# SCH_NFC-Card_2024-10-16.net
KiCad netlist of a schematic drawn in EasyEDA
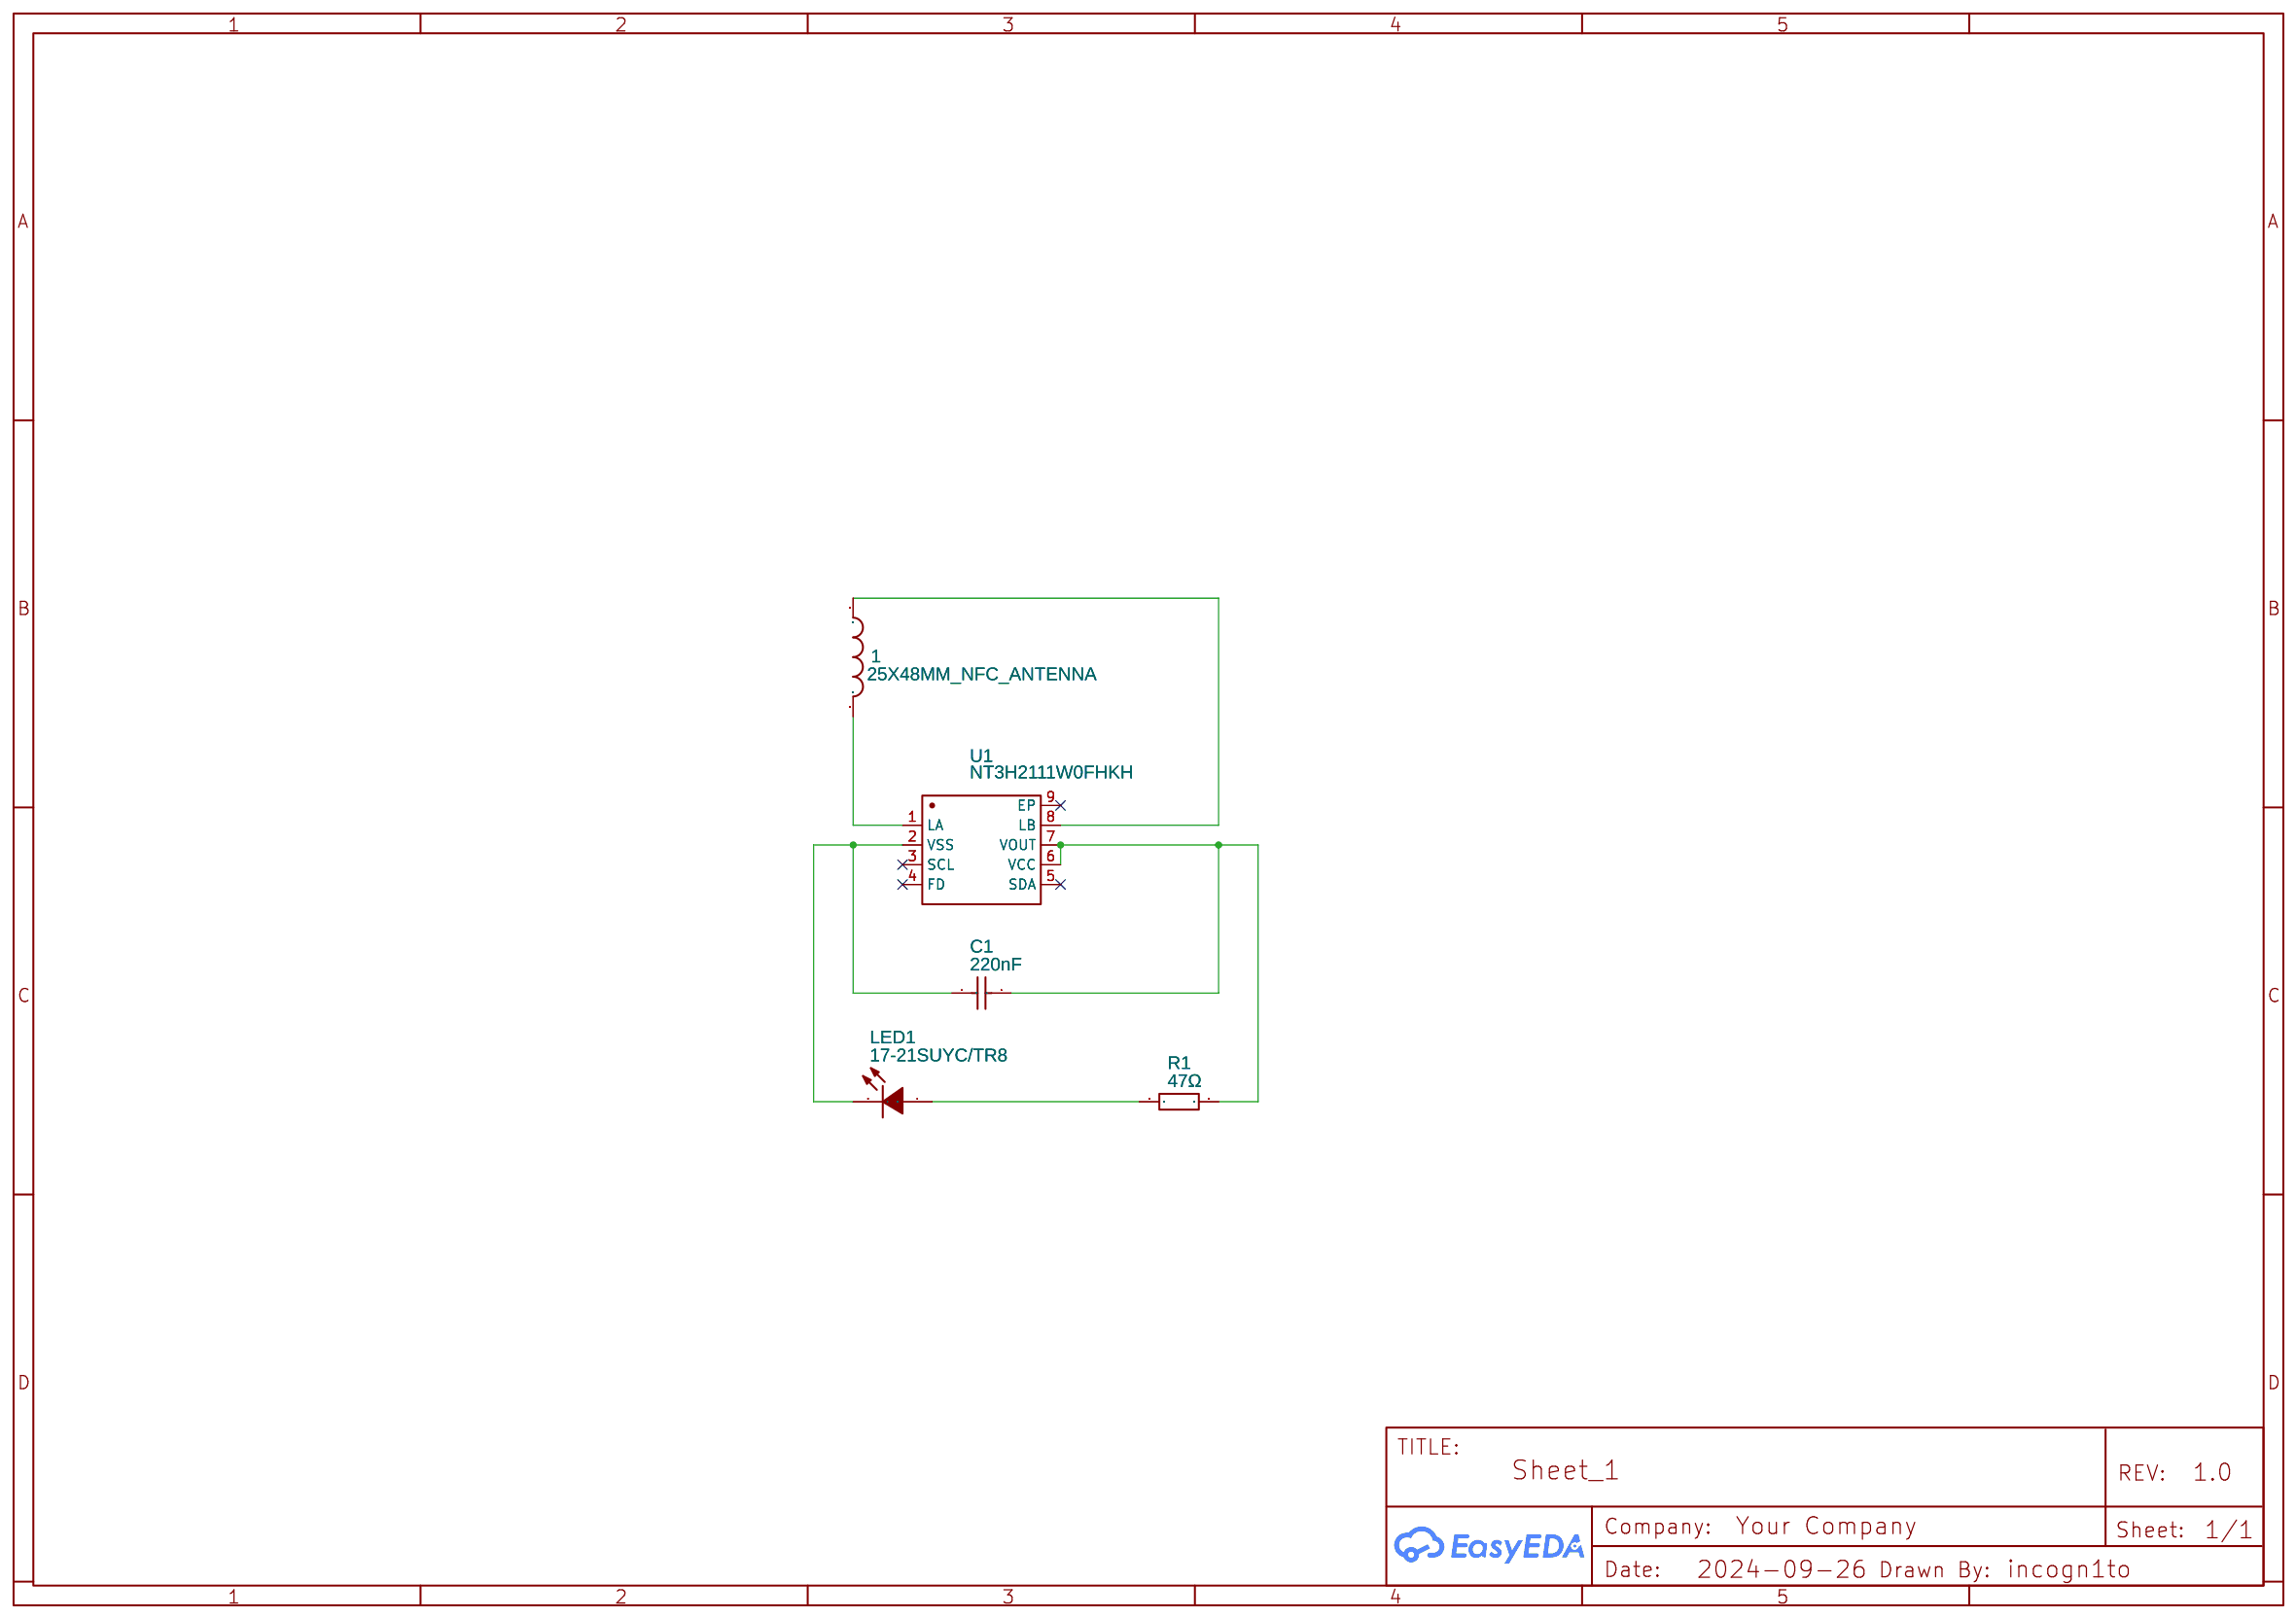
[diagram p0: schematic sheet]

(export (version "E")
  (design (tool "Eeschema 10.0.6"))
  (components
    (comp (ref "1") (value "25X48MM_NFC_ANTENNA") (libsource (lib "") (part "25X48MM_NFC_ANTENNA")))
    (comp (ref "C1")
      (value "220nF")
      (fields
        (field (name "Manufacturer Part") "CL10B224KA8NNNC")
        (field (name "Manufacturer") "SAMSUNG(三星)")
      )
      (libsource (lib "") (part "CL10B224KA8NNNC"))
    )
    (comp (ref "LED1")
      (value "17-21SUYC/TR8")
      (fields (field (name "Manufacturer Part") "KT-0805黄灯") (field (name "Manufacturer") "KENTO"))
      (libsource (lib "") (part "17-21SUYC/TR8"))
    )
    (comp (ref "R1")
      (value "47Ω")
      (fields
        (field (name "Manufacturer Part") "0603WAF470JT5E")
        (field (name "Manufacturer") "UNI-ROYAL(厚声)")
      )
      (libsource (lib "") (part "0603WAF470JT5E"))
    )
    (comp (ref "U1")
      (value "NT3H2111W0FHKH")
      (fields (field (name "Manufacturer") "NXP(恩智浦)"))
      (libsource (lib "") (part "NT3H2111W0FHKH"))
    )
  )
  (nets
    (net (code "1") (name "Net-(LED1-+)") (class "Default")
      (node (ref "LED1") (pin "1") (pinfunction "+_1") (pintype "unspecified"))
      (node (ref "R1") (pin "1") (pinfunction "1_1") (pintype "input"))
    )
    (net (code "2") (name "Net-(LED1--)") (class "Default")
      (node (ref "C1") (pin "1") (pinfunction "1_1") (pintype "input"))
      (node (ref "LED1") (pin "2") (pinfunction "-_2") (pintype "unspecified"))
      (node (ref "U1") (pin "2") (pinfunction "VSS_2") (pintype "unspecified"))
    )
    (net (code "3") (name "Net-(U1-LA)") (class "Default")
      (node (ref "1") (pin "P$2") (pinfunction "P$2_P$2") (pintype "bidirectional"))
      (node (ref "U1") (pin "1") (pinfunction "LA_1") (pintype "unspecified"))
    )
    (net (code "4") (name "Net-(U1-LB)") (class "Default")
      (node (ref "1") (pin "P$1") (pinfunction "P$1_P$1") (pintype "bidirectional"))
      (node (ref "U1") (pin "8") (pinfunction "LB_8") (pintype "unspecified"))
    )
    (net (code "5") (name "Net-(U1-VCC)") (class "Default")
      (node (ref "C1") (pin "2") (pinfunction "2_2") (pintype "input"))
      (node (ref "R1") (pin "2") (pinfunction "2_2") (pintype "input"))
      (node (ref "U1") (pin "6") (pinfunction "VCC_6") (pintype "unspecified"))
      (node (ref "U1") (pin "7") (pinfunction "VOUT_7") (pintype "unspecified"))
    )
    (net (code "6") (name "unconnected-(U1-EP-Pad9)") (class "Default")
      (node (ref "U1") (pin "9") (pinfunction "EP_9") (pintype "unspecified+no_connect"))
    )
    (net (code "7") (name "unconnected-(U1-FD-Pad4)") (class "Default")
      (node (ref "U1") (pin "4") (pinfunction "FD_4") (pintype "unspecified+no_connect"))
    )
    (net (code "8") (name "unconnected-(U1-SCL-Pad3)") (class "Default")
      (node (ref "U1") (pin "3") (pinfunction "SCL_3") (pintype "unspecified+no_connect"))
    )
    (net (code "9") (name "unconnected-(U1-SDA-Pad5)") (class "Default")
      (node (ref "U1") (pin "5") (pinfunction "SDA_5") (pintype "unspecified+no_connect"))
    )
  )
)
